# TMS570LS1224_Microcontroller.net
KiCad netlist of a schematic drawn in Altium Designer
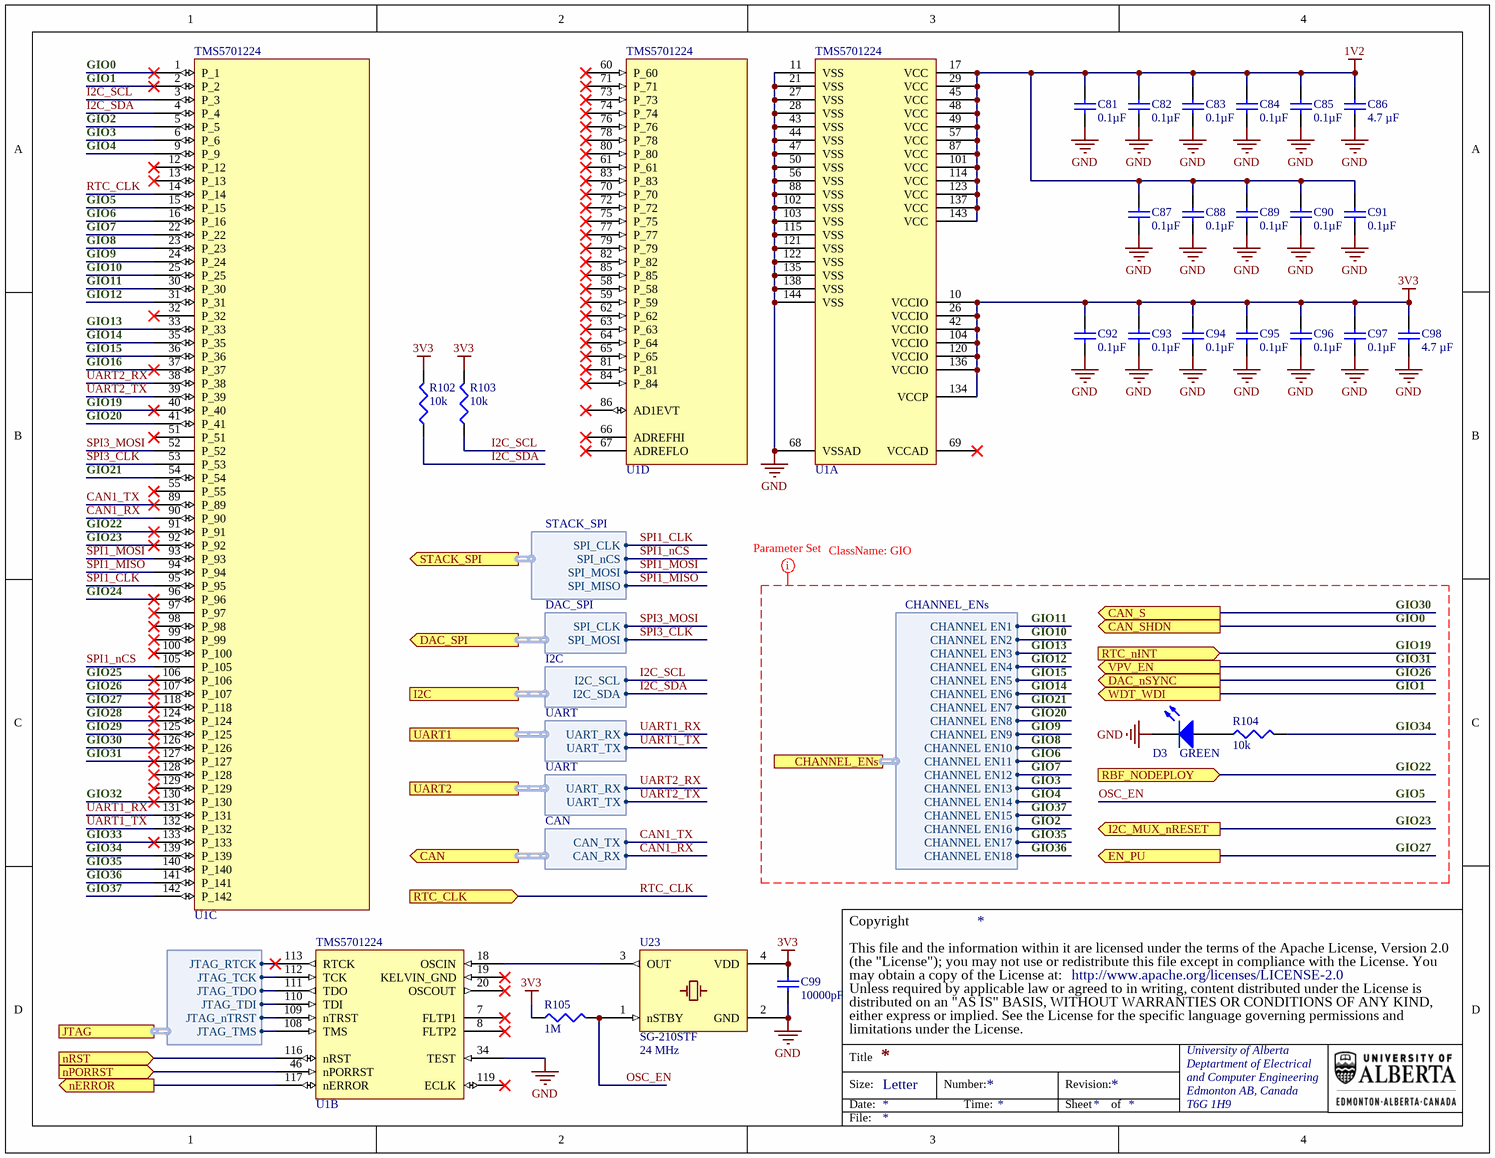
[diagram p0: TMS570LS1224 Microcontroller.SchDoc]

(export (version "E")
  (design (tool "Eeschema 10.0.6"))
  (components
    (comp (ref "C81")
      (value "0.1µF")
      (footprint "TDK-CGA2B")
      (description "CAP CER 0.1UF 50V X7R 0402")
      (fields
        (field (name "PART NUMBER") "PC-TDK-02259")
        (field (name "MANUFACTURER PART NUMBER") "CGA2B3X7R1H104K050BB")
        (field (name "PUBLISHER") "AlbertaSat")
      )
      (libsource (lib "Database") (part "Cap"))
    )
    (comp (ref "C82")
      (value "0.1µF")
      (footprint "TDK-CGA2B")
      (description "CAP CER 0.1UF 50V X7R 0402")
      (fields
        (field (name "PART NUMBER") "PC-TDK-02259")
        (field (name "MANUFACTURER PART NUMBER") "CGA2B3X7R1H104K050BB")
        (field (name "PUBLISHER") "AlbertaSat")
      )
      (libsource (lib "Database") (part "Cap"))
    )
    (comp (ref "C83")
      (value "0.1µF")
      (footprint "TDK-CGA2B")
      (description "CAP CER 0.1UF 50V X7R 0402")
      (fields
        (field (name "PART NUMBER") "PC-TDK-02259")
        (field (name "MANUFACTURER PART NUMBER") "CGA2B3X7R1H104K050BB")
        (field (name "PUBLISHER") "AlbertaSat")
      )
      (libsource (lib "Database") (part "Cap"))
    )
    (comp (ref "C84")
      (value "0.1µF")
      (footprint "TDK-CGA2B")
      (description "CAP CER 0.1UF 50V X7R 0402")
      (fields
        (field (name "PART NUMBER") "PC-TDK-02259")
        (field (name "MANUFACTURER PART NUMBER") "CGA2B3X7R1H104K050BB")
        (field (name "PUBLISHER") "AlbertaSat")
      )
      (libsource (lib "Database") (part "Cap"))
    )
    (comp (ref "C85")
      (value "0.1µF")
      (footprint "TDK-CGA2B")
      (description "CAP CER 0.1UF 50V X7R 0402")
      (fields
        (field (name "PART NUMBER") "PC-TDK-02259")
        (field (name "MANUFACTURER PART NUMBER") "CGA2B3X7R1H104K050BB")
        (field (name "PUBLISHER") "AlbertaSat")
      )
      (libsource (lib "Database") (part "Cap"))
    )
    (comp (ref "C86")
      (value "4.7 µF")
      (footprint "MUR-GRM188")
      (description "CAP CER 4.7UF 16V X7R 0603")
      (fields
        (field (name "PART NUMBER") "10165")
        (field (name "MANUFACTURER PART NUMBER") "GRM188Z71C475KE21D")
        (field (name "PUBLISHER") "Altium Limited")
      )
      (libsource (lib "Database") (part "Cap"))
    )
    (comp (ref "C87")
      (value "0.1µF")
      (footprint "TDK-CGA2B")
      (description "CAP CER 0.1UF 50V X7R 0402")
      (fields
        (field (name "PART NUMBER") "PC-TDK-02259")
        (field (name "MANUFACTURER PART NUMBER") "CGA2B3X7R1H104K050BB")
        (field (name "PUBLISHER") "AlbertaSat")
      )
      (libsource (lib "Database") (part "Cap"))
    )
    (comp (ref "C88")
      (value "0.1µF")
      (footprint "TDK-CGA2B")
      (description "CAP CER 0.1UF 50V X7R 0402")
      (fields
        (field (name "PART NUMBER") "PC-TDK-02259")
        (field (name "MANUFACTURER PART NUMBER") "CGA2B3X7R1H104K050BB")
        (field (name "PUBLISHER") "AlbertaSat")
      )
      (libsource (lib "Database") (part "Cap"))
    )
    (comp (ref "C89")
      (value "0.1µF")
      (footprint "TDK-CGA2B")
      (description "CAP CER 0.1UF 50V X7R 0402")
      (fields
        (field (name "PART NUMBER") "PC-TDK-02259")
        (field (name "MANUFACTURER PART NUMBER") "CGA2B3X7R1H104K050BB")
        (field (name "PUBLISHER") "AlbertaSat")
      )
      (libsource (lib "Database") (part "Cap"))
    )
    (comp (ref "C90")
      (value "0.1µF")
      (footprint "TDK-CGA2B")
      (description "CAP CER 0.1UF 50V X7R 0402")
      (fields
        (field (name "PART NUMBER") "PC-TDK-02259")
        (field (name "MANUFACTURER PART NUMBER") "CGA2B3X7R1H104K050BB")
        (field (name "PUBLISHER") "AlbertaSat")
      )
      (libsource (lib "Database") (part "Cap"))
    )
    (comp (ref "C91")
      (value "0.1µF")
      (footprint "TDK-CGA2B")
      (description "CAP CER 0.1UF 50V X7R 0402")
      (fields
        (field (name "PART NUMBER") "PC-TDK-02259")
        (field (name "MANUFACTURER PART NUMBER") "CGA2B3X7R1H104K050BB")
        (field (name "PUBLISHER") "AlbertaSat")
      )
      (libsource (lib "Database") (part "Cap"))
    )
    (comp (ref "C92")
      (value "0.1µF")
      (footprint "TDK-CGA2B")
      (description "CAP CER 0.1UF 50V X7R 0402")
      (fields
        (field (name "PART NUMBER") "PC-TDK-02259")
        (field (name "MANUFACTURER PART NUMBER") "CGA2B3X7R1H104K050BB")
        (field (name "PUBLISHER") "AlbertaSat")
      )
      (libsource (lib "Database") (part "Cap"))
    )
    (comp (ref "C93")
      (value "0.1µF")
      (footprint "TDK-CGA2B")
      (description "CAP CER 0.1UF 50V X7R 0402")
      (fields
        (field (name "PART NUMBER") "PC-TDK-02259")
        (field (name "MANUFACTURER PART NUMBER") "CGA2B3X7R1H104K050BB")
        (field (name "PUBLISHER") "AlbertaSat")
      )
      (libsource (lib "Database") (part "Cap"))
    )
    (comp (ref "C94")
      (value "0.1µF")
      (footprint "TDK-CGA2B")
      (description "CAP CER 0.1UF 50V X7R 0402")
      (fields
        (field (name "PART NUMBER") "PC-TDK-02259")
        (field (name "MANUFACTURER PART NUMBER") "CGA2B3X7R1H104K050BB")
        (field (name "PUBLISHER") "AlbertaSat")
      )
      (libsource (lib "Database") (part "Cap"))
    )
    (comp (ref "C95")
      (value "0.1µF")
      (footprint "TDK-CGA2B")
      (description "CAP CER 0.1UF 50V X7R 0402")
      (fields
        (field (name "PART NUMBER") "PC-TDK-02259")
        (field (name "MANUFACTURER PART NUMBER") "CGA2B3X7R1H104K050BB")
        (field (name "PUBLISHER") "AlbertaSat")
      )
      (libsource (lib "Database") (part "Cap"))
    )
    (comp (ref "C96")
      (value "0.1µF")
      (footprint "TDK-CGA2B")
      (description "CAP CER 0.1UF 50V X7R 0402")
      (fields
        (field (name "PART NUMBER") "PC-TDK-02259")
        (field (name "MANUFACTURER PART NUMBER") "CGA2B3X7R1H104K050BB")
        (field (name "PUBLISHER") "AlbertaSat")
      )
      (libsource (lib "Database") (part "Cap"))
    )
    (comp (ref "C97")
      (value "0.1µF")
      (footprint "TDK-CGA2B")
      (description "CAP CER 0.1UF 50V X7R 0402")
      (fields
        (field (name "PART NUMBER") "PC-TDK-02259")
        (field (name "MANUFACTURER PART NUMBER") "CGA2B3X7R1H104K050BB")
        (field (name "PUBLISHER") "AlbertaSat")
      )
      (libsource (lib "Database") (part "Cap"))
    )
    (comp (ref "C98")
      (value "4.7 µF")
      (footprint "MUR-GRM188")
      (description "CAP CER 4.7UF 16V X7R 0603")
      (fields
        (field (name "PART NUMBER") "10165")
        (field (name "MANUFACTURER PART NUMBER") "GRM188Z71C475KE21D")
        (field (name "PUBLISHER") "Altium Limited")
      )
      (libsource (lib "Database") (part "Cap"))
    )
    (comp (ref "C99")
      (value "10000pF")
      (footprint "TDK-CGA2B")
      (description "CAP CER 10000PF 50V X8R 0402")
      (fields
        (field (name "PART NUMBER") "PC-TDK-01877")
        (field (name "MANUFACTURER PART NUMBER") "CGA2B3X8R1H103K050BB")
        (field (name "PUBLISHER") "AlbertaSat")
      )
      (libsource (lib "Database") (part "Cap"))
    )
    (comp (ref "D3")
      (value "GREEN")
      (footprint "WL-150060XS75000")
      (description "LED GREEN CLEAR 0603 SMD")
      (fields
        (field (name "PART NUMBER") "2")
        (field (name "MANUFACTURER PART NUMBER") "150060GS75000")
        (field (name "PUBLISHER") "Altium Limited")
      )
      (libsource (lib "Database") (part "LED0"))
    )
    (comp (ref "R102")
      (value "10k")
      (footprint "PANA-ERJ2R")
      (description "RES SMD 10K OHM 1% 1/10W 0402")
      (fields
        (field (name "PART NUMBER") "17198")
        (field (name "MANUFACTURER PART NUMBER") "ERJ-2RKF1002X")
        (field (name "PUBLISHER") "Altium Limited")
      )
      (libsource (lib "Database") (part "Res3"))
    )
    (comp (ref "R103")
      (value "10k")
      (footprint "PANA-ERJ2R")
      (description "RES SMD 10K OHM 1% 1/10W 0402")
      (fields
        (field (name "PART NUMBER") "17198")
        (field (name "MANUFACTURER PART NUMBER") "ERJ-2RKF1002X")
        (field (name "PUBLISHER") "Altium Limited")
      )
      (libsource (lib "Database") (part "Res3"))
    )
    (comp (ref "R104")
      (value "10k")
      (footprint "PANA-ERJ2R")
      (description "RES SMD 10K OHM 1% 1/10W 0402")
      (fields
        (field (name "PART NUMBER") "17198")
        (field (name "MANUFACTURER PART NUMBER") "ERJ-2RKF1002X")
        (field (name "PUBLISHER") "Altium Limited")
      )
      (libsource (lib "Database") (part "Res3"))
    )
    (comp (ref "R105")
      (value "1M")
      (footprint "PANA-ERJ2R")
      (description "RES SMD 1M OHM 1% 1/10W 0402")
      (fields
        (field (name "PART NUMBER") "19704")
        (field (name "MANUFACTURER PART NUMBER") "ERJ-2RKF1004X")
        (field (name "PUBLISHER") "Altium Limited")
      )
      (libsource (lib "Database") (part "Res3"))
    )
    (comp (ref "U1")
      (value "TMS5701224")
      (footprint "TI-S-PQFP-G144")
      (description "IC MCU 32BIT 1.25MB FLASH 144QFP")
      (fields (field (name "PART NUMBER") "59") (field (name "MANUFACTURER PART NUMBER") "TMS5701224CPGEQQ1"))
      (libsource (lib "Database") (part "TMS5701224CPGEQQ1"))
    )
    (comp (ref "U23")
      (value "SG-210STF")
      (footprint "EPS-SG-210STF")
      (description "XTAL OSC XO 24.0000MHZ CMOS SMD")
      (fields
        (field (name "PART NUMBER") "PU-EPS-00002")
        (field (name "MANUFACTURER PART NUMBER") "SG-210STF 24.0000MY0")
        (field (name "ALTIUM_VALUE") "24 MHz")
        (field (name "PUBLISHER") "AlbertaSat")
      )
      (libsource (lib "Database") (part "SG-210STF"))
    )
  )
  (nets
    (net (code "8") (name "/CAN1_RX") (class "Default")
      (node (ref "U1") (pin "90") (pinfunction "P_90_90") (pintype "bidirectional"))
    )
    (net (code "9") (name "/CAN1_TX") (class "Default")
      (node (ref "U1") (pin "89") (pinfunction "P_89_89") (pintype "bidirectional"))
    )
    (net (code "10") (name "/GIO0") (class "Default")
      (node (ref "U1") (pin "1") (pinfunction "P_1_1") (pintype "bidirectional"))
    )
    (net (code "11") (name "/GIO1") (class "Default")
      (node (ref "U1") (pin "2") (pinfunction "P_2_2") (pintype "bidirectional"))
    )
    (net (code "12") (name "/GIO2") (class "Default")
      (node (ref "U1") (pin "5") (pinfunction "P_5_5") (pintype "bidirectional"))
    )
    (net (code "13") (name "/GIO3") (class "Default")
      (node (ref "U1") (pin "6") (pinfunction "P_6_6") (pintype "bidirectional"))
    )
    (net (code "14") (name "/GIO4") (class "Default")
      (node (ref "U1") (pin "9") (pinfunction "P_9_9") (pintype "bidirectional"))
    )
    (net (code "15") (name "/GIO5") (class "Default")
      (node (ref "R105") (pin "1") (pinfunction "1_1") (pintype "passive"))
      (node (ref "U1") (pin "15") (pinfunction "P_15_15") (pintype "bidirectional"))
      (node (ref "U23") (pin "1") (pinfunction "nSTBY_1") (pintype "input"))
    )
    (net (code "16") (name "/GIO6") (class "Default")
      (node (ref "U1") (pin "16") (pinfunction "P_16_16") (pintype "bidirectional"))
    )
    (net (code "17") (name "/GIO7") (class "Default")
      (node (ref "U1") (pin "22") (pinfunction "P_22_22") (pintype "bidirectional"))
    )
    (net (code "18") (name "/GIO8") (class "Default")
      (node (ref "U1") (pin "23") (pinfunction "P_23_23") (pintype "bidirectional"))
    )
    (net (code "19") (name "/GIO9") (class "Default")
      (node (ref "U1") (pin "24") (pinfunction "P_24_24") (pintype "bidirectional"))
    )
    (net (code "20") (name "/GIO10") (class "Default")
      (node (ref "U1") (pin "25") (pinfunction "P_25_25") (pintype "bidirectional"))
    )
    (net (code "21") (name "/GIO11") (class "Default")
      (node (ref "U1") (pin "30") (pinfunction "P_30_30") (pintype "bidirectional"))
    )
    (net (code "22") (name "/GIO12") (class "Default")
      (node (ref "U1") (pin "31") (pinfunction "P_31_31") (pintype "bidirectional"))
    )
    (net (code "23") (name "/GIO13") (class "Default")
      (node (ref "U1") (pin "33") (pinfunction "P_33_33") (pintype "bidirectional"))
    )
    (net (code "24") (name "/GIO14") (class "Default")
      (node (ref "U1") (pin "35") (pinfunction "P_35_35") (pintype "bidirectional"))
    )
    (net (code "25") (name "/GIO15") (class "Default")
      (node (ref "U1") (pin "36") (pinfunction "P_36_36") (pintype "bidirectional"))
    )
    (net (code "26") (name "/GIO16") (class "Default")
      (node (ref "U1") (pin "37") (pinfunction "P_37_37") (pintype "bidirectional+no_connect"))
    )
    (net (code "27") (name "/GIO19") (class "Default")
      (node (ref "U1") (pin "40") (pinfunction "P_40_40") (pintype "bidirectional"))
    )
    (net (code "28") (name "/GIO20") (class "Default")
      (node (ref "U1") (pin "41") (pinfunction "P_41_41") (pintype "bidirectional"))
    )
    (net (code "29") (name "/GIO21") (class "Default")
      (node (ref "U1") (pin "54") (pinfunction "P_54_54") (pintype "bidirectional"))
    )
    (net (code "30") (name "/GIO22") (class "Default")
      (node (ref "U1") (pin "91") (pinfunction "P_91_91") (pintype "bidirectional"))
    )
    (net (code "31") (name "/GIO23") (class "Default")
      (node (ref "U1") (pin "92") (pinfunction "P_92_92") (pintype "bidirectional"))
    )
    (net (code "32") (name "/GIO24") (class "Default")
      (node (ref "U1") (pin "96") (pinfunction "P_96_96") (pintype "bidirectional+no_connect"))
    )
    (net (code "33") (name "/GIO25") (class "Default")
      (node (ref "U1") (pin "106") (pinfunction "P_106_106") (pintype "bidirectional+no_connect"))
    )
    (net (code "34") (name "/GIO26") (class "Default")
      (node (ref "U1") (pin "107") (pinfunction "P_107_107") (pintype "bidirectional"))
    )
    (net (code "35") (name "/GIO27") (class "Default")
      (node (ref "U1") (pin "118") (pinfunction "P_118_118") (pintype "bidirectional"))
    )
    (net (code "36") (name "/GIO28") (class "Default")
      (node (ref "U1") (pin "124") (pinfunction "P_124_124") (pintype "bidirectional+no_connect"))
    )
    (net (code "37") (name "/GIO29") (class "Default")
      (node (ref "U1") (pin "125") (pinfunction "P_125_125") (pintype "bidirectional+no_connect"))
    )
    (net (code "38") (name "/GIO30") (class "Default")
      (node (ref "U1") (pin "126") (pinfunction "P_126_126") (pintype "bidirectional"))
    )
    (net (code "39") (name "/GIO31") (class "Default")
      (node (ref "U1") (pin "127") (pinfunction "P_127_127") (pintype "bidirectional"))
    )
    (net (code "40") (name "/GIO32") (class "Default")
      (node (ref "U1") (pin "130") (pinfunction "P_130_130") (pintype "bidirectional+no_connect"))
    )
    (net (code "41") (name "/GIO33") (class "Default")
      (node (ref "U1") (pin "133") (pinfunction "P_133_133") (pintype "bidirectional+no_connect"))
    )
    (net (code "42") (name "/GIO34") (class "Default")
      (node (ref "R104") (pin "1") (pinfunction "1_1") (pintype "passive"))
      (node (ref "U1") (pin "139") (pinfunction "P_139_139") (pintype "bidirectional"))
    )
    (net (code "43") (name "/GIO35") (class "Default")
      (node (ref "U1") (pin "140") (pinfunction "P_140_140") (pintype "bidirectional"))
    )
    (net (code "44") (name "/GIO36") (class "Default")
      (node (ref "U1") (pin "141") (pinfunction "P_141_141") (pintype "bidirectional"))
    )
    (net (code "45") (name "/GIO37") (class "Default")
      (node (ref "U1") (pin "142") (pinfunction "P_142_142") (pintype "bidirectional"))
    )
    (net (code "46") (name "/I2C_SCL") (class "Default")
      (node (ref "R103") (pin "2") (pinfunction "2_2") (pintype "passive"))
      (node (ref "U1") (pin "3") (pinfunction "P_3_3") (pintype "bidirectional"))
    )
    (net (code "47") (name "/I2C_SDA") (class "Default")
      (node (ref "R102") (pin "2") (pinfunction "2_2") (pintype "passive"))
      (node (ref "U1") (pin "4") (pinfunction "P_4_4") (pintype "bidirectional"))
    )
    (net (code "48") (name "/JTAG_RTCK") (class "Default")
      (node (ref "U1") (pin "113") (pinfunction "RTCK_113") (pintype "output+no_connect"))
    )
    (net (code "49") (name "/JTAG_TCK") (class "Default")
      (node (ref "U1") (pin "112") (pinfunction "TCK_112") (pintype "input"))
    )
    (net (code "50") (name "/JTAG_TDI") (class "Default")
      (node (ref "U1") (pin "110") (pinfunction "TDI_110") (pintype "input"))
    )
    (net (code "51") (name "/JTAG_TDO") (class "Default")
      (node (ref "U1") (pin "111") (pinfunction "TDO_111") (pintype "output"))
    )
    (net (code "52") (name "/JTAG_TMS") (class "Default")
      (node (ref "U1") (pin "108") (pinfunction "TMS_108") (pintype "input"))
    )
    (net (code "53") (name "/JTAG_nTRST") (class "Default")
      (node (ref "U1") (pin "109") (pinfunction "nTRST_109") (pintype "input"))
    )
    (net (code "54") (name "/RTC_CLK") (class "Default")
      (node (ref "U1") (pin "14") (pinfunction "P_14_14") (pintype "bidirectional"))
    )
    (net (code "55") (name "/SPI1_CLK") (class "Default")
      (node (ref "U1") (pin "95") (pinfunction "P_95_95") (pintype "bidirectional"))
    )
    (net (code "56") (name "/SPI1_MISO") (class "Default")
      (node (ref "U1") (pin "94") (pinfunction "P_94_94") (pintype "bidirectional"))
    )
    (net (code "57") (name "/SPI1_MOSI") (class "Default")
      (node (ref "U1") (pin "93") (pinfunction "P_93_93") (pintype "bidirectional"))
    )
    (net (code "58") (name "/SPI1_nCS") (class "Default")
      (node (ref "U1") (pin "105") (pinfunction "P_105_105") (pintype "passive"))
    )
    (net (code "59") (name "/SPI3_CLK") (class "Default")
      (node (ref "U1") (pin "53") (pinfunction "P_53_53") (pintype "passive"))
    )
    (net (code "60") (name "/SPI3_MOSI") (class "Default")
      (node (ref "U1") (pin "52") (pinfunction "P_52_52") (pintype "passive"))
    )
    (net (code "61") (name "/UART1_RX") (class "Default")
      (node (ref "U1") (pin "131") (pinfunction "P_131_131") (pintype "bidirectional"))
    )
    (net (code "62") (name "/UART1_TX") (class "Default")
      (node (ref "U1") (pin "132") (pinfunction "P_132_132") (pintype "bidirectional"))
    )
    (net (code "63") (name "/UART2_RX") (class "Default")
      (node (ref "U1") (pin "38") (pinfunction "P_38_38") (pintype "bidirectional"))
    )
    (net (code "64") (name "/UART2_TX") (class "Default")
      (node (ref "U1") (pin "39") (pinfunction "P_39_39") (pintype "bidirectional"))
    )
    (net (code "65") (name "/nERROR") (class "Default")
      (node (ref "U1") (pin "117") (pinfunction "nERROR_117") (pintype "bidirectional"))
    )
    (net (code "66") (name "/nPORRST") (class "Default")
      (node (ref "U1") (pin "46") (pinfunction "nPORRST_46") (pintype "input"))
    )
    (net (code "67") (name "/nRST") (class "Default")
      (node (ref "U1") (pin "116") (pinfunction "nRST_116") (pintype "bidirectional"))
    )
    (net (code "75") (name "1V2") (class "Default")
      (node (ref "C81") (pin "2") (pinfunction "2_2") (pintype "passive"))
      (node (ref "C82") (pin "2") (pinfunction "2_2") (pintype "passive"))
      (node (ref "C83") (pin "2") (pinfunction "2_2") (pintype "passive"))
      (node (ref "C84") (pin "2") (pinfunction "2_2") (pintype "passive"))
      (node (ref "C85") (pin "2") (pinfunction "2_2") (pintype "passive"))
      (node (ref "C86") (pin "2") (pinfunction "2_2") (pintype "passive"))
      (node (ref "C87") (pin "2") (pinfunction "2_2") (pintype "passive"))
      (node (ref "C88") (pin "2") (pinfunction "2_2") (pintype "passive"))
      (node (ref "C89") (pin "2") (pinfunction "2_2") (pintype "passive"))
      (node (ref "C90") (pin "2") (pinfunction "2_2") (pintype "passive"))
      (node (ref "C91") (pin "2") (pinfunction "2_2") (pintype "passive"))
      (node (ref "U1") (pin "101") (pinfunction "VCC_101") (pintype "power_in"))
      (node (ref "U1") (pin "114") (pinfunction "VCC_114") (pintype "power_in"))
      (node (ref "U1") (pin "123") (pinfunction "VCC_123") (pintype "power_in"))
      (node (ref "U1") (pin "137") (pinfunction "VCC_137") (pintype "power_in"))
      (node (ref "U1") (pin "143") (pinfunction "VCC_143") (pintype "power_in"))
      (node (ref "U1") (pin "17") (pinfunction "VCC_17") (pintype "power_in"))
      (node (ref "U1") (pin "29") (pinfunction "VCC_29") (pintype "power_in"))
      (node (ref "U1") (pin "45") (pinfunction "VCC_45") (pintype "power_in"))
      (node (ref "U1") (pin "48") (pinfunction "VCC_48") (pintype "power_in"))
      (node (ref "U1") (pin "49") (pinfunction "VCC_49") (pintype "power_in"))
      (node (ref "U1") (pin "57") (pinfunction "VCC_57") (pintype "power_in"))
      (node (ref "U1") (pin "87") (pinfunction "VCC_87") (pintype "power_in"))
    )
    (net (code "76") (name "3V3") (class "Default")
      (node (ref "C92") (pin "2") (pinfunction "2_2") (pintype "passive"))
      (node (ref "C93") (pin "2") (pinfunction "2_2") (pintype "passive"))
      (node (ref "C94") (pin "2") (pinfunction "2_2") (pintype "passive"))
      (node (ref "C95") (pin "2") (pinfunction "2_2") (pintype "passive"))
      (node (ref "C96") (pin "2") (pinfunction "2_2") (pintype "passive"))
      (node (ref "C97") (pin "2") (pinfunction "2_2") (pintype "passive"))
      (node (ref "C98") (pin "2") (pinfunction "2_2") (pintype "passive"))
      (node (ref "C99") (pin "2") (pinfunction "2_2") (pintype "passive"))
      (node (ref "R102") (pin "1") (pinfunction "1_1") (pintype "passive"))
      (node (ref "R103") (pin "1") (pinfunction "1_1") (pintype "passive"))
      (node (ref "R105") (pin "2") (pinfunction "2_2") (pintype "passive"))
      (node (ref "U1") (pin "10") (pinfunction "VCCIO_10") (pintype "power_in"))
      (node (ref "U1") (pin "104") (pinfunction "VCCIO_104") (pintype "power_in"))
      (node (ref "U1") (pin "120") (pinfunction "VCCIO_120") (pintype "power_in"))
      (node (ref "U1") (pin "134") (pinfunction "VCCP_134") (pintype "power_in"))
      (node (ref "U1") (pin "136") (pinfunction "VCCIO_136") (pintype "power_in"))
      (node (ref "U1") (pin "26") (pinfunction "VCCIO_26") (pintype "power_in"))
      (node (ref "U1") (pin "42") (pinfunction "VCCIO_42") (pintype "power_in"))
      (node (ref "U23") (pin "4") (pinfunction "VDD_4") (pintype "power_in"))
    )
    (net (code "77") (name "GND") (class "Default")
      (node (ref "C81") (pin "1") (pinfunction "1_1") (pintype "passive"))
      (node (ref "C82") (pin "1") (pinfunction "1_1") (pintype "passive"))
      (node (ref "C83") (pin "1") (pinfunction "1_1") (pintype "passive"))
      (node (ref "C84") (pin "1") (pinfunction "1_1") (pintype "passive"))
      (node (ref "C85") (pin "1") (pinfunction "1_1") (pintype "passive"))
      (node (ref "C86") (pin "1") (pinfunction "1_1") (pintype "passive"))
      (node (ref "C87") (pin "1") (pinfunction "1_1") (pintype "passive"))
      (node (ref "C88") (pin "1") (pinfunction "1_1") (pintype "passive"))
      (node (ref "C89") (pin "1") (pinfunction "1_1") (pintype "passive"))
      (node (ref "C90") (pin "1") (pinfunction "1_1") (pintype "passive"))
      (node (ref "C91") (pin "1") (pinfunction "1_1") (pintype "passive"))
      (node (ref "C92") (pin "1") (pinfunction "1_1") (pintype "passive"))
      (node (ref "C93") (pin "1") (pinfunction "1_1") (pintype "passive"))
      (node (ref "C94") (pin "1") (pinfunction "1_1") (pintype "passive"))
      (node (ref "C95") (pin "1") (pinfunction "1_1") (pintype "passive"))
      (node (ref "C96") (pin "1") (pinfunction "1_1") (pintype "passive"))
      (node (ref "C97") (pin "1") (pinfunction "1_1") (pintype "passive"))
      (node (ref "C98") (pin "1") (pinfunction "1_1") (pintype "passive"))
      (node (ref "C99") (pin "1") (pinfunction "1_1") (pintype "passive"))
      (node (ref "D3") (pin "2") (pinfunction "K_2") (pintype "passive"))
      (node (ref "U1") (pin "102") (pinfunction "VSS_102") (pintype "power_in"))
      (node (ref "U1") (pin "103") (pinfunction "VSS_103") (pintype "power_in"))
      (node (ref "U1") (pin "11") (pinfunction "VSS_11") (pintype "power_in"))
      (node (ref "U1") (pin "115") (pinfunction "VSS_115") (pintype "power_in"))
      (node (ref "U1") (pin "121") (pinfunction "VSS_121") (pintype "power_in"))
      (node (ref "U1") (pin "122") (pinfunction "VSS_122") (pintype "power_in"))
      (node (ref "U1") (pin "135") (pinfunction "VSS_135") (pintype "power_in"))
      (node (ref "U1") (pin "138") (pinfunction "VSS_138") (pintype "power_in"))
      (node (ref "U1") (pin "144") (pinfunction "VSS_144") (pintype "power_in"))
      (node (ref "U1") (pin "21") (pinfunction "VSS_21") (pintype "power_in"))
      (node (ref "U1") (pin "27") (pinfunction "VSS_27") (pintype "power_in"))
      (node (ref "U1") (pin "28") (pinfunction "VSS_28") (pintype "power_in"))
      (node (ref "U1") (pin "34") (pinfunction "TEST_34") (pintype "input"))
      (node (ref "U1") (pin "43") (pinfunction "VSS_43") (pintype "power_in"))
      (node (ref "U1") (pin "44") (pinfunction "VSS_44") (pintype "power_in"))
      (node (ref "U1") (pin "47") (pinfunction "VSS_47") (pintype "power_in"))
      (node (ref "U1") (pin "50") (pinfunction "VSS_50") (pintype "power_in"))
      (node (ref "U1") (pin "56") (pinfunction "VSS_56") (pintype "power_in"))
      (node (ref "U1") (pin "68") (pinfunction "VSSAD_68") (pintype "power_in"))
      (node (ref "U1") (pin "88") (pinfunction "VSS_88") (pintype "power_in"))
      (node (ref "U23") (pin "2") (pinfunction "GND_2") (pintype "power_in"))
    )
    (net (code "78") (name "Net-(D3-A)") (class "Default")
      (node (ref "D3") (pin "1") (pinfunction "A_1") (pintype "passive"))
      (node (ref "R104") (pin "2") (pinfunction "2_2") (pintype "passive"))
    )
    (net (code "79") (name "Net-(U1B-OSCIN)") (class "Default")
      (node (ref "U1") (pin "18") (pinfunction "OSCIN_18") (pintype "input"))
      (node (ref "U23") (pin "3") (pinfunction "OUT_3") (pintype "output"))
    )
    (net (code "80") (name "unconnected-(U1A-VCCAD-Pad69)") (class "Default")
      (node (ref "U1") (pin "69") (pinfunction "VCCAD_69") (pintype "power_in+no_connect"))
    )
    (net (code "81") (name "unconnected-(U1B-ECLK-Pad119)") (class "Default")
      (node (ref "U1") (pin "119") (pinfunction "ECLK_119") (pintype "bidirectional+no_connect"))
    )
    (net (code "82") (name "unconnected-(U1B-FLTP1-Pad7)") (class "Default")
      (node (ref "U1") (pin "7") (pinfunction "FLTP1_7") (pintype "passive+no_connect"))
    )
    (net (code "83") (name "unconnected-(U1B-FLTP2-Pad8)") (class "Default")
      (node (ref "U1") (pin "8") (pinfunction "FLTP2_8") (pintype "passive+no_connect"))
    )
    (net (code "84") (name "unconnected-(U1B-KELVIN_GND-Pad19)") (class "Default")
      (node (ref "U1") (pin "19") (pinfunction "KELVIN_GND_19") (pintype "input+no_connect"))
    )
    (net (code "85") (name "unconnected-(U1B-OSCOUT-Pad20)") (class "Default")
      (node (ref "U1") (pin "20") (pinfunction "OSCOUT_20") (pintype "output+no_connect"))
    )
    (net (code "86") (name "unconnected-(U1C-P_12-Pad12)") (class "Default")
      (node (ref "U1") (pin "12") (pinfunction "P_12_12") (pintype "bidirectional+no_connect"))
    )
    (net (code "87") (name "unconnected-(U1C-P_13-Pad13)") (class "Default")
      (node (ref "U1") (pin "13") (pinfunction "P_13_13") (pintype "bidirectional+no_connect"))
    )
    (net (code "88") (name "unconnected-(U1C-P_32-Pad32)") (class "Default")
      (node (ref "U1") (pin "32") (pinfunction "P_32_32") (pintype "passive+no_connect"))
    )
    (net (code "89") (name "unconnected-(U1C-P_51-Pad51)") (class "Default")
      (node (ref "U1") (pin "51") (pinfunction "P_51_51") (pintype "passive+no_connect"))
    )
    (net (code "90") (name "unconnected-(U1C-P_55-Pad55)") (class "Default")
      (node (ref "U1") (pin "55") (pinfunction "P_55_55") (pintype "passive+no_connect"))
    )
    (net (code "91") (name "unconnected-(U1C-P_97-Pad97)") (class "Default")
      (node (ref "U1") (pin "97") (pinfunction "P_97_97") (pintype "passive+no_connect"))
    )
    (net (code "92") (name "unconnected-(U1C-P_98-Pad98)") (class "Default")
      (node (ref "U1") (pin "98") (pinfunction "P_98_98") (pintype "bidirectional+no_connect"))
    )
    (net (code "93") (name "unconnected-(U1C-P_99-Pad99)") (class "Default")
      (node (ref "U1") (pin "99") (pinfunction "P_99_99") (pintype "bidirectional+no_connect"))
    )
    (net (code "94") (name "unconnected-(U1C-P_100-Pad100)") (class "Default")
      (node (ref "U1") (pin "100") (pinfunction "P_100_100") (pintype "bidirectional+no_connect"))
    )
    (net (code "95") (name "unconnected-(U1C-P_128-Pad128)") (class "Default")
      (node (ref "U1") (pin "128") (pinfunction "P_128_128") (pintype "bidirectional+no_connect"))
    )
    (net (code "96") (name "unconnected-(U1C-P_129-Pad129)") (class "Default")
      (node (ref "U1") (pin "129") (pinfunction "P_129_129") (pintype "bidirectional+no_connect"))
    )
    (net (code "97") (name "unconnected-(U1D-AD1EVT-Pad86)") (class "Default")
      (node (ref "U1") (pin "86") (pinfunction "AD1EVT_86") (pintype "bidirectional+no_connect"))
    )
    (net (code "98") (name "unconnected-(U1D-ADREFHI-Pad66)") (class "Default")
      (node (ref "U1") (pin "66") (pinfunction "ADREFHI_66") (pintype "power_in+no_connect"))
    )
    (net (code "99") (name "unconnected-(U1D-ADREFLO-Pad67)") (class "Default")
      (node (ref "U1") (pin "67") (pinfunction "ADREFLO_67") (pintype "power_in+no_connect"))
    )
    (net (code "100") (name "unconnected-(U1D-P_58-Pad58)") (class "Default")
      (node (ref "U1") (pin "58") (pinfunction "P_58_58") (pintype "input+no_connect"))
    )
    (net (code "101") (name "unconnected-(U1D-P_59-Pad59)") (class "Default")
      (node (ref "U1") (pin "59") (pinfunction "P_59_59") (pintype "input+no_connect"))
    )
    (net (code "102") (name "unconnected-(U1D-P_60-Pad60)") (class "Default")
      (node (ref "U1") (pin "60") (pinfunction "P_60_60") (pintype "input+no_connect"))
    )
    (net (code "103") (name "unconnected-(U1D-P_61-Pad61)") (class "Default")
      (node (ref "U1") (pin "61") (pinfunction "P_61_61") (pintype "input+no_connect"))
    )
    (net (code "104") (name "unconnected-(U1D-P_62-Pad62)") (class "Default")
      (node (ref "U1") (pin "62") (pinfunction "P_62_62") (pintype "input+no_connect"))
    )
    (net (code "105") (name "unconnected-(U1D-P_63-Pad63)") (class "Default")
      (node (ref "U1") (pin "63") (pinfunction "P_63_63") (pintype "input+no_connect"))
    )
    (net (code "106") (name "unconnected-(U1D-P_64-Pad64)") (class "Default")
      (node (ref "U1") (pin "64") (pinfunction "P_64_64") (pintype "input+no_connect"))
    )
    (net (code "107") (name "unconnected-(U1D-P_65-Pad65)") (class "Default")
      (node (ref "U1") (pin "65") (pinfunction "P_65_65") (pintype "input+no_connect"))
    )
    (net (code "108") (name "unconnected-(U1D-P_70-Pad70)") (class "Default")
      (node (ref "U1") (pin "70") (pinfunction "P_70_70") (pintype "input+no_connect"))
    )
    (net (code "109") (name "unconnected-(U1D-P_71-Pad71)") (class "Default")
      (node (ref "U1") (pin "71") (pinfunction "P_71_71") (pintype "input+no_connect"))
    )
    (net (code "110") (name "unconnected-(U1D-P_72-Pad72)") (class "Default")
      (node (ref "U1") (pin "72") (pinfunction "P_72_72") (pintype "input+no_connect"))
    )
    (net (code "111") (name "unconnected-(U1D-P_73-Pad73)") (class "Default")
      (node (ref "U1") (pin "73") (pinfunction "P_73_73") (pintype "input+no_connect"))
    )
    (net (code "112") (name "unconnected-(U1D-P_74-Pad74)") (class "Default")
      (node (ref "U1") (pin "74") (pinfunction "P_74_74") (pintype "input+no_connect"))
    )
    (net (code "113") (name "unconnected-(U1D-P_75-Pad75)") (class "Default")
      (node (ref "U1") (pin "75") (pinfunction "P_75_75") (pintype "input+no_connect"))
    )
    (net (code "114") (name "unconnected-(U1D-P_76-Pad76)") (class "Default")
      (node (ref "U1") (pin "76") (pinfunction "P_76_76") (pintype "input+no_connect"))
    )
    (net (code "115") (name "unconnected-(U1D-P_77-Pad77)") (class "Default")
      (node (ref "U1") (pin "77") (pinfunction "P_77_77") (pintype "input+no_connect"))
    )
    (net (code "116") (name "unconnected-(U1D-P_78-Pad78)") (class "Default")
      (node (ref "U1") (pin "78") (pinfunction "P_78_78") (pintype "input+no_connect"))
    )
    (net (code "117") (name "unconnected-(U1D-P_79-Pad79)") (class "Default")
      (node (ref "U1") (pin "79") (pinfunction "P_79_79") (pintype "input+no_connect"))
    )
    (net (code "118") (name "unconnected-(U1D-P_80-Pad80)") (class "Default")
      (node (ref "U1") (pin "80") (pinfunction "P_80_80") (pintype "input+no_connect"))
    )
    (net (code "119") (name "unconnected-(U1D-P_81-Pad81)") (class "Default")
      (node (ref "U1") (pin "81") (pinfunction "P_81_81") (pintype "input+no_connect"))
    )
    (net (code "120") (name "unconnected-(U1D-P_82-Pad82)") (class "Default")
      (node (ref "U1") (pin "82") (pinfunction "P_82_82") (pintype "input+no_connect"))
    )
    (net (code "121") (name "unconnected-(U1D-P_83-Pad83)") (class "Default")
      (node (ref "U1") (pin "83") (pinfunction "P_83_83") (pintype "input+no_connect"))
    )
    (net (code "122") (name "unconnected-(U1D-P_84-Pad84)") (class "Default")
      (node (ref "U1") (pin "84") (pinfunction "P_84_84") (pintype "input+no_connect"))
    )
    (net (code "123") (name "unconnected-(U1D-P_85-Pad85)") (class "Default")
      (node (ref "U1") (pin "85") (pinfunction "P_85_85") (pintype "input+no_connect"))
    )
  )
)
